# Current_Sense.net
KiCad netlist of a schematic drawn in Altium Designer
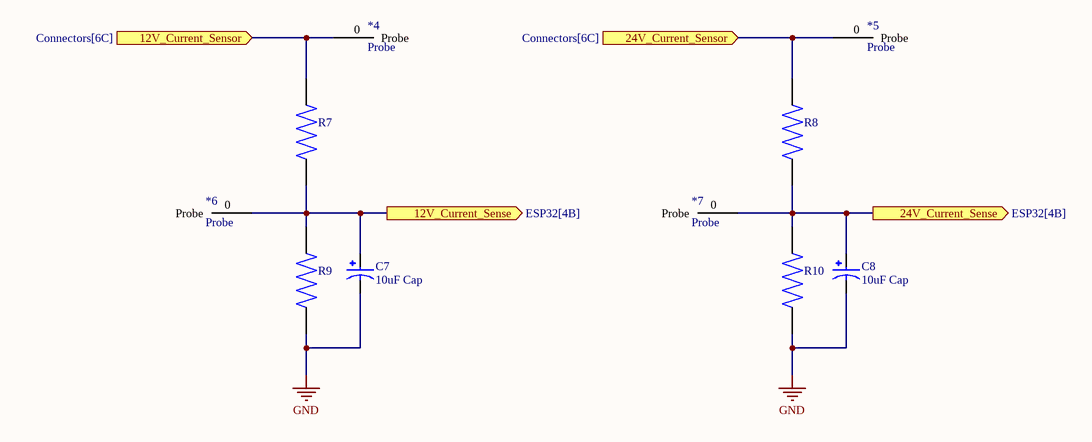
[diagram p0: Current Sense.SchDoc]

(export (version "E")
  (design (tool "Eeschema 10.0.6"))
  (components
    (comp (ref "*4") (value "Probe") (footprint "Probe") (libsource (lib "MySCH_Library") (part "Probe")))
    (comp (ref "*5") (value "Probe") (footprint "Probe") (libsource (lib "MySCH_Library") (part "Probe")))
    (comp (ref "*6") (value "Probe") (footprint "Probe") (libsource (lib "MySCH_Library") (part "Probe")))
    (comp (ref "*7") (value "Probe") (footprint "Probe") (libsource (lib "MySCH_Library") (part "Probe")))
    (comp (ref "C7")
      (value "10uF Cap")
      (footprint "CAP_10uF")
      (description "CAP ALUM 10UF 20% 50V RADIAL")
      (fields (field (name "MP") "ECE-A1HN100UI") (field (name "MF") "Panasonic"))
      (libsource (lib "MySCH_Library") (part "10uF Cap"))
    )
    (comp (ref "C8")
      (value "10uF Cap")
      (footprint "CAP_10uF")
      (description "CAP ALUM 10UF 20% 50V RADIAL")
      (fields (field (name "MP") "ECE-A1HN100UI") (field (name "MF") "Panasonic"))
      (libsource (lib "MySCH_Library") (part "10uF Cap"))
    )
    (comp (ref "R7")
      (value "Resistor_Through Hole")
      (footprint "Resistor_Through Hole")
      (description "1.02 Ohms Â±1% 0.25W, 1/4W Through Hole Resistor Axial Metal Film")
      (fields (field (name "MP") "MFR-25FTE52-1R") (field (name "MF") "Yageo"))
      (libsource (lib "MySCH_Library") (part "Resistor_Through Hole"))
    )
    (comp (ref "R8")
      (value "Resistor_Through Hole")
      (footprint "Resistor_Through Hole")
      (description "1.02 Ohms Â±1% 0.25W, 1/4W Through Hole Resistor Axial Metal Film")
      (fields (field (name "MP") "MFR-25FTE52-1R") (field (name "MF") "Yageo"))
      (libsource (lib "MySCH_Library") (part "Resistor_Through Hole"))
    )
    (comp (ref "R9")
      (value "Resistor_Through Hole")
      (footprint "Resistor_Through Hole")
      (description "1.02 Ohms Â±1% 0.25W, 1/4W Through Hole Resistor Axial Metal Film")
      (fields (field (name "MP") "MFR-25FTE52-1R") (field (name "MF") "Yageo"))
      (libsource (lib "MySCH_Library") (part "Resistor_Through Hole"))
    )
    (comp (ref "R10")
      (value "Resistor_Through Hole")
      (footprint "Resistor_Through Hole")
      (description "1.02 Ohms Â±1% 0.25W, 1/4W Through Hole Resistor Axial Metal Film")
      (fields (field (name "MP") "MFR-25FTE52-1R") (field (name "MF") "Yageo"))
      (libsource (lib "MySCH_Library") (part "Resistor_Through Hole"))
    )
  )
  (nets
    (net (code "1") (name "/12V_Current_Sense") (class "Default")
      (node (ref "*6") (pin "0") (pinfunction "Probe_0") (pintype "passive"))
      (node (ref "C7") (pin "P") (pinfunction "P_P") (pintype "passive"))
      (node (ref "R7") (pin "1") (pinfunction "1_1") (pintype "passive"))
      (node (ref "R9") (pin "2") (pinfunction "2_2") (pintype "passive"))
    )
    (net (code "2") (name "/12V_Current_Sensor") (class "Default")
      (node (ref "*4") (pin "0") (pinfunction "Probe_0") (pintype "passive"))
      (node (ref "R7") (pin "2") (pinfunction "2_2") (pintype "passive"))
    )
    (net (code "3") (name "/24V_Current_Sense") (class "Default")
      (node (ref "*7") (pin "0") (pinfunction "Probe_0") (pintype "passive"))
      (node (ref "C8") (pin "P") (pinfunction "P_P") (pintype "passive"))
      (node (ref "R10") (pin "2") (pinfunction "2_2") (pintype "passive"))
      (node (ref "R8") (pin "1") (pinfunction "1_1") (pintype "passive"))
    )
    (net (code "4") (name "/24V_Current_Sensor") (class "Default")
      (node (ref "*5") (pin "0") (pinfunction "Probe_0") (pintype "passive"))
      (node (ref "R8") (pin "2") (pinfunction "2_2") (pintype "passive"))
    )
    (net (code "5") (name "GND") (class "Default")
      (node (ref "C7") (pin "N") (pinfunction "N_N") (pintype "passive"))
      (node (ref "C8") (pin "N") (pinfunction "N_N") (pintype "passive"))
      (node (ref "R10") (pin "1") (pinfunction "1_1") (pintype "passive"))
      (node (ref "R9") (pin "1") (pinfunction "1_1") (pintype "passive"))
    )
  )
)
